# VoiceRecognitionGroup3.net
KiCad netlist of a schematic drawn in EAGLE
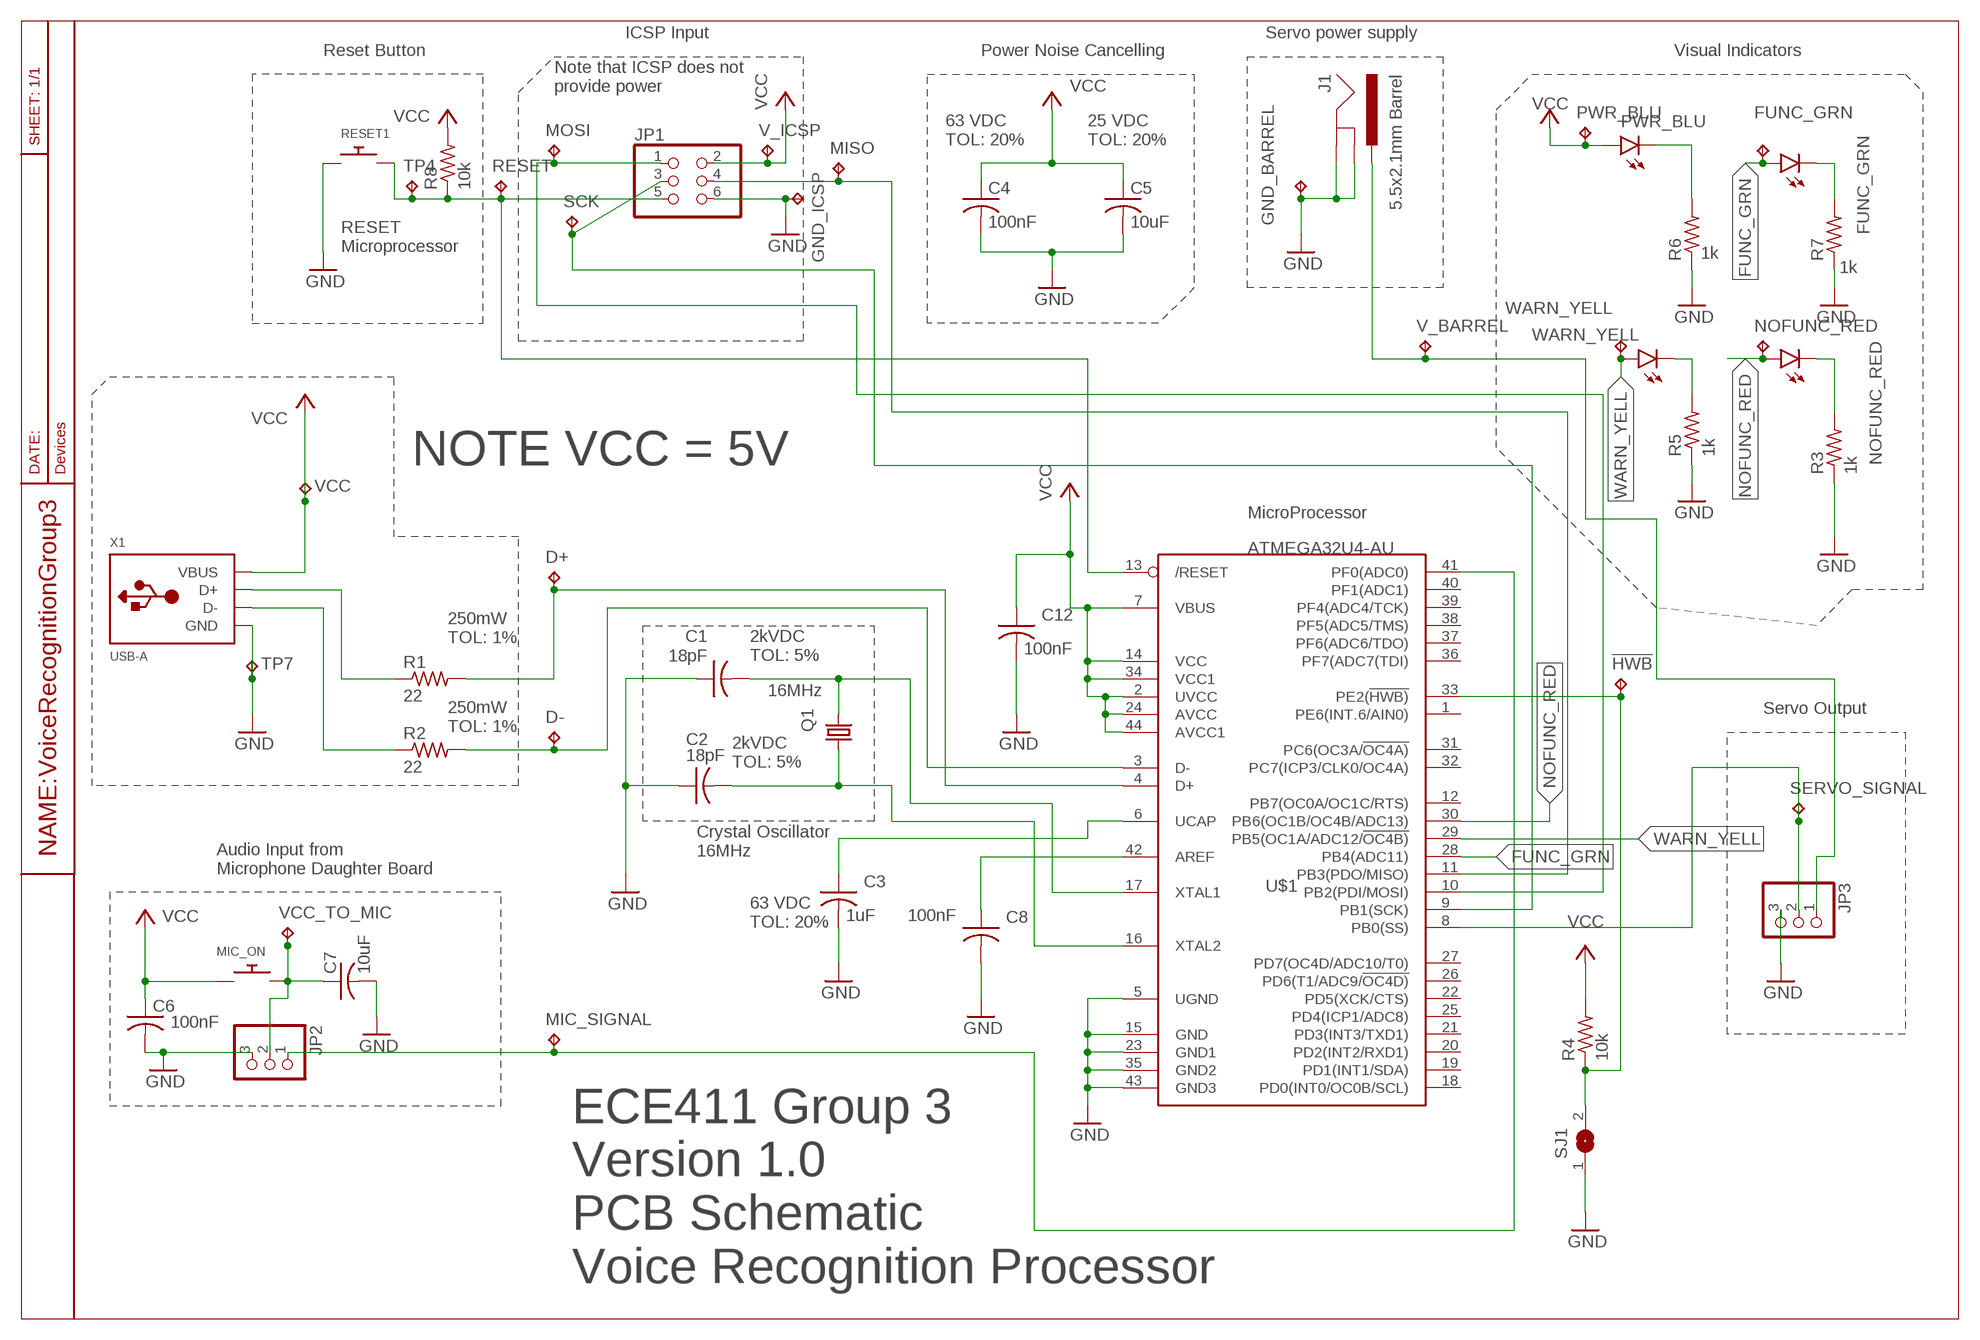
[diagram p0: schematic, sheet 1]

(export (version "E")
  (design (tool "Eeschema 10.0.6"))
  (components
    (comp (ref "!HWB")
      (value "TPTP15SQ")
      (footprint "eagle-import:TP15SQ")
      (libsource (lib "eagle-import") (part "TPTP15SQ"))
    )
    (comp (ref "C1")
      (value "18pF")
      (footprint "eagle-import:C1206")
      (libsource (lib "eagle-import") (part "C-USC1206"))
    )
    (comp (ref "C2")
      (value "18pF")
      (footprint "eagle-import:C1206")
      (libsource (lib "eagle-import") (part "C-USC1206"))
    )
    (comp (ref "C3")
      (value "1uF")
      (footprint "eagle-import:C1206")
      (libsource (lib "eagle-import") (part "C-USC1206"))
    )
    (comp (ref "C4")
      (value "100nF")
      (footprint "eagle-import:C1206")
      (libsource (lib "eagle-import") (part "C-USC1206"))
    )
    (comp (ref "C5")
      (value "10uF")
      (footprint "eagle-import:C1206")
      (libsource (lib "eagle-import") (part "C-USC1206"))
    )
    (comp (ref "C6")
      (value "100nF")
      (footprint "eagle-import:C1206")
      (libsource (lib "eagle-import") (part "C-USC1206"))
    )
    (comp (ref "C7")
      (value "10uF")
      (footprint "eagle-import:C1206")
      (libsource (lib "eagle-import") (part "C-USC1206"))
    )
    (comp (ref "C8")
      (value "100nF")
      (footprint "eagle-import:C1206")
      (libsource (lib "eagle-import") (part "C-USC1206"))
    )
    (comp (ref "C12")
      (value "100nF")
      (footprint "eagle-import:C1206")
      (libsource (lib "eagle-import") (part "C-USC1206"))
    )
    (comp (ref "D+")
      (value "TPTP15SQ")
      (footprint "eagle-import:TP15SQ")
      (libsource (lib "eagle-import") (part "TPTP15SQ"))
    )
    (comp (ref "D-")
      (value "TPTP15SQ")
      (footprint "eagle-import:TP15SQ")
      (libsource (lib "eagle-import") (part "TPTP15SQ"))
    )
    (comp (ref "FUNC_GRN")
      (value "TPTP15SQ")
      (footprint "eagle-import:TP15SQ")
      (libsource (lib "eagle-import") (part "TPTP15SQ"))
    )
    (comp (ref "GND_BARREL")
      (value "TPTP15SQ")
      (footprint "eagle-import:TP15SQ")
      (libsource (lib "eagle-import") (part "TPTP15SQ"))
    )
    (comp (ref "GND_ICSP")
      (value "TPTP15SQ")
      (footprint "eagle-import:TP15SQ")
      (libsource (lib "eagle-import") (part "TPTP15SQ"))
    )
    (comp (ref "J1")
      (value "5.5x2.1mm Barrel")
      (footprint "eagle-import:POWER_JACK_SMD")
      (libsource (lib "eagle-import") (part "POWER_JACKSMD"))
    )
    (comp (ref "JP1")
      (value "PINHD-2X3")
      (footprint "eagle-import:2X03")
      (libsource (lib "eagle-import") (part "PINHD-2X3"))
    )
    (comp (ref "JP2")
      (value "PINHD-1X3")
      (footprint "eagle-import:1X03")
      (libsource (lib "eagle-import") (part "PINHD-1X3"))
    )
    (comp (ref "JP3")
      (value "PINHD-1X3")
      (footprint "eagle-import:1X03")
      (libsource (lib "eagle-import") (part "PINHD-1X3"))
    )
    (comp (ref "LED2")
      (value "LEDSMT1206")
      (footprint "eagle-import:1206")
      (libsource (lib "eagle-import") (part "LEDSMT1206"))
    )
    (comp (ref "LED3")
      (value "LEDSMT1206")
      (footprint "eagle-import:1206")
      (libsource (lib "eagle-import") (part "LEDSMT1206"))
    )
    (comp (ref "LED4")
      (value "LEDSMT1206")
      (footprint "eagle-import:1206")
      (libsource (lib "eagle-import") (part "LEDSMT1206"))
    )
    (comp (ref "MIC_ON")
      (value "SWITCH_PUSHBUTTONC&K_KSS")
      (footprint "eagle-import:BTN_CK_KSS")
      (libsource (lib "eagle-import") (part "SWITCH_PUSHBUTTONC&K_KSS"))
    )
    (comp (ref "MIC_SIGNAL")
      (value "TPTP15SQ")
      (footprint "eagle-import:TP15SQ")
      (libsource (lib "eagle-import") (part "TPTP15SQ"))
    )
    (comp (ref "MISO")
      (value "TPTP15SQ")
      (footprint "eagle-import:TP15SQ")
      (libsource (lib "eagle-import") (part "TPTP15SQ"))
    )
    (comp (ref "MOSI")
      (value "TPTP15SQ")
      (footprint "eagle-import:TP15SQ")
      (libsource (lib "eagle-import") (part "TPTP15SQ"))
    )
    (comp (ref "NOFUNC_RED")
      (value "TPTP15SQ")
      (footprint "eagle-import:TP15SQ")
      (libsource (lib "eagle-import") (part "TPTP15SQ"))
    )
    (comp (ref "PWR-BLU")
      (value "LEDSMT1206")
      (footprint "eagle-import:1206")
      (libsource (lib "eagle-import") (part "LEDSMT1206"))
    )
    (comp (ref "PWR_BLU")
      (value "TPTP15SQ")
      (footprint "eagle-import:TP15SQ")
      (libsource (lib "eagle-import") (part "TPTP15SQ"))
    )
    (comp (ref "Q1")
      (value "16MHz")
      (footprint "eagle-import:CTS406")
      (libsource (lib "eagle-import") (part "CRYSTALCTS406"))
    )
    (comp (ref "R1")
      (value "22")
      (footprint "eagle-import:M1206")
      (libsource (lib "eagle-import") (part "R-US_M1206"))
    )
    (comp (ref "R2")
      (value "22")
      (footprint "eagle-import:M1206")
      (libsource (lib "eagle-import") (part "R-US_M1206"))
    )
    (comp (ref "R3")
      (value "1k")
      (footprint "eagle-import:M1206")
      (libsource (lib "eagle-import") (part "R-US_M1206"))
    )
    (comp (ref "R4")
      (value "10k")
      (footprint "eagle-import:M1206")
      (libsource (lib "eagle-import") (part "R-US_M1206"))
    )
    (comp (ref "R5")
      (value "1k")
      (footprint "eagle-import:M1206")
      (libsource (lib "eagle-import") (part "R-US_M1206"))
    )
    (comp (ref "R6")
      (value "1k")
      (footprint "eagle-import:M1206")
      (libsource (lib "eagle-import") (part "R-US_M1206"))
    )
    (comp (ref "R7")
      (value "1k")
      (footprint "eagle-import:M1206")
      (libsource (lib "eagle-import") (part "R-US_M1206"))
    )
    (comp (ref "R8")
      (value "10k")
      (footprint "eagle-import:M1206")
      (libsource (lib "eagle-import") (part "R-US_M1206"))
    )
    (comp (ref "RESET")
      (value "TPTP15SQ")
      (footprint "eagle-import:TP15SQ")
      (libsource (lib "eagle-import") (part "TPTP15SQ"))
    )
    (comp (ref "RESET1")
      (value "SWITCH_PUSHBUTTONC&K_KSS")
      (footprint "eagle-import:BTN_CK_KSS")
      (libsource (lib "eagle-import") (part "SWITCH_PUSHBUTTONC&K_KSS"))
    )
    (comp (ref "SCK")
      (value "TPTP15SQ")
      (footprint "eagle-import:TP15SQ")
      (libsource (lib "eagle-import") (part "TPTP15SQ"))
    )
    (comp (ref "SERVO_SIGNAL")
      (value "TPTP15SQ")
      (footprint "eagle-import:TP15SQ")
      (libsource (lib "eagle-import") (part "TPTP15SQ"))
    )
    (comp (ref "SJ1")
      (value "SJW")
      (footprint "eagle-import:SJW")
      (libsource (lib "eagle-import") (part "SJW"))
    )
    (comp (ref "TP4")
      (value "TPTP15SQ")
      (footprint "eagle-import:TP15SQ")
      (libsource (lib "eagle-import") (part "TPTP15SQ"))
    )
    (comp (ref "TP7")
      (value "TPTP15SQ")
      (footprint "eagle-import:TP15SQ")
      (libsource (lib "eagle-import") (part "TPTP15SQ"))
    )
    (comp (ref "U$1")
      (value "ATMEGA32U4-AU")
      (footprint "eagle-import:TQFP44")
      (libsource (lib "eagle-import") (part "ATMEGA32U4-AU"))
    )
    (comp (ref "VCC")
      (value "TPTP15SQ")
      (footprint "eagle-import:TP15SQ")
      (libsource (lib "eagle-import") (part "TPTP15SQ"))
    )
    (comp (ref "VCC_TO_MIC")
      (value "TPTP15SQ")
      (footprint "eagle-import:TP15SQ")
      (libsource (lib "eagle-import") (part "TPTP15SQ"))
    )
    (comp (ref "V_BARREL")
      (value "TPTP15SQ")
      (footprint "eagle-import:TP15SQ")
      (libsource (lib "eagle-import") (part "TPTP15SQ"))
    )
    (comp (ref "V_ICSP")
      (value "TPTP15SQ")
      (footprint "eagle-import:TP15SQ")
      (libsource (lib "eagle-import") (part "TPTP15SQ"))
    )
    (comp (ref "WARN_YELL")
      (value "TPTP15SQ")
      (footprint "eagle-import:TP15SQ")
      (libsource (lib "eagle-import") (part "TPTP15SQ"))
    )
    (comp (ref "X1")
      (value "USB-A")
      (footprint "eagle-import:MOLEX_480371000")
      (libsource (lib "eagle-import") (part "USB-A"))
    )
  )
  (nets
    (net (code "1") (name "FUNC_GRN") (class "Default")
      (node (ref "FUNC_GRN") (pin "TP") (pinfunction "TP_TP") (pintype "input"))
      (node (ref "LED2") (pin "A") (pinfunction "A_A") (pintype "passive"))
      (node (ref "U$1") (pin "28") (pinfunction "PB4(ADC11)_28") (pintype "bidirectional"))
    )
    (net (code "2") (name "GND") (class "Default")
      (node (ref "C1") (pin "1") (pinfunction "1_1") (pintype "passive"))
      (node (ref "C12") (pin "2") (pinfunction "2_2") (pintype "passive"))
      (node (ref "C2") (pin "1") (pinfunction "1_1") (pintype "passive"))
      (node (ref "C3") (pin "2") (pinfunction "2_2") (pintype "passive"))
      (node (ref "C4") (pin "2") (pinfunction "2_2") (pintype "passive"))
      (node (ref "C5") (pin "2") (pinfunction "2_2") (pintype "passive"))
      (node (ref "C6") (pin "2") (pinfunction "2_2") (pintype "passive"))
      (node (ref "C7") (pin "2") (pinfunction "2_2") (pintype "passive"))
      (node (ref "C8") (pin "2") (pinfunction "2_2") (pintype "passive"))
      (node (ref "GND_BARREL") (pin "TP") (pinfunction "TP_TP") (pintype "input"))
      (node (ref "GND_ICSP") (pin "TP") (pinfunction "TP_TP") (pintype "input"))
      (node (ref "J1") (pin "GND") (pinfunction "GNDBREAK_GND") (pintype "bidirectional"))
      (node (ref "J1") (pin "P$4") (pinfunction "GND_P$4") (pintype "bidirectional"))
      (node (ref "JP1") (pin "6") (pinfunction "6_6") (pintype "passive"))
      (node (ref "JP2") (pin "3") (pinfunction "3_3") (pintype "passive"))
      (node (ref "JP3") (pin "3") (pinfunction "3_3") (pintype "passive"))
      (node (ref "R3") (pin "1") (pinfunction "1_1") (pintype "passive"))
      (node (ref "R5") (pin "1") (pinfunction "1_1") (pintype "passive"))
      (node (ref "R6") (pin "1") (pinfunction "1_1") (pintype "passive"))
      (node (ref "R7") (pin "1") (pinfunction "1_1") (pintype "passive"))
      (node (ref "RESET1") (pin "P$1") (pinfunction "P$1_P$1") (pintype "passive"))
      (node (ref "SJ1") (pin "1") (pinfunction "1_1") (pintype "passive"))
      (node (ref "TP7") (pin "TP") (pinfunction "TP_TP") (pintype "input"))
      (node (ref "U$1") (pin "15") (pinfunction "GND_15") (pintype "bidirectional"))
      (node (ref "U$1") (pin "23") (pinfunction "GND1_23") (pintype "bidirectional"))
      (node (ref "U$1") (pin "35") (pinfunction "GND2_35") (pintype "bidirectional"))
      (node (ref "U$1") (pin "43") (pinfunction "GND3_43") (pintype "bidirectional"))
      (node (ref "U$1") (pin "5") (pinfunction "UGND_5") (pintype "bidirectional"))
      (node (ref "X1") (pin "4") (pinfunction "GND_4") (pintype "power_in"))
    )
    (net (code "3") (name "NOFUNC_RED") (class "Default")
      (node (ref "LED3") (pin "A") (pinfunction "A_A") (pintype "passive"))
      (node (ref "NOFUNC_RED") (pin "TP") (pinfunction "TP_TP") (pintype "input"))
      (node (ref "U$1") (pin "30") (pinfunction "PB6(OC1B/OC4B/ADC13)_30") (pintype "bidirectional"))
    )
    (net (code "4") (name "Net-(C7-Pad1)") (class "Default")
      (node (ref "C7") (pin "1") (pinfunction "1_1") (pintype "passive"))
      (node (ref "JP2") (pin "2") (pinfunction "2_2") (pintype "passive"))
      (node (ref "MIC_ON") (pin "P$2") (pinfunction "P$2_P$2") (pintype "passive"))
      (node (ref "VCC_TO_MIC") (pin "TP") (pinfunction "TP_TP") (pintype "input"))
    )
    (net (code "5") (name "Net-(J1-PWR)") (class "Default")
      (node (ref "J1") (pin "VIN0") (pinfunction "PWR_VIN0") (pintype "bidirectional"))
      (node (ref "JP3") (pin "1") (pinfunction "1_1") (pintype "passive"))
      (node (ref "V_BARREL") (pin "TP") (pinfunction "TP_TP") (pintype "input"))
    )
    (net (code "6") (name "Net-(LED2-PadC)") (class "Default")
      (node (ref "LED2") (pin "C") (pinfunction "C_C") (pintype "passive"))
      (node (ref "R7") (pin "2") (pinfunction "2_2") (pintype "passive"))
    )
    (net (code "7") (name "Net-(LED3-PadC)") (class "Default")
      (node (ref "LED3") (pin "C") (pinfunction "C_C") (pintype "passive"))
      (node (ref "R3") (pin "2") (pinfunction "2_2") (pintype "passive"))
    )
    (net (code "8") (name "Net-(LED4-PadC)") (class "Default")
      (node (ref "LED4") (pin "C") (pinfunction "C_C") (pintype "passive"))
      (node (ref "R5") (pin "2") (pinfunction "2_2") (pintype "passive"))
    )
    (net (code "9") (name "Net-(PWR-BLU-PadC)") (class "Default")
      (node (ref "PWR-BLU") (pin "C") (pinfunction "C_C") (pintype "passive"))
      (node (ref "R6") (pin "2") (pinfunction "2_2") (pintype "passive"))
    )
    (net (code "10") (name "Net-(Q1-2)") (class "Default")
      (node (ref "C1") (pin "2") (pinfunction "2_2") (pintype "passive"))
      (node (ref "Q1") (pin "3") (pinfunction "2_3") (pintype "passive"))
      (node (ref "U$1") (pin "17") (pinfunction "XTAL1_17") (pintype "bidirectional"))
    )
    (net (code "11") (name "Net-(U$1-AREF)") (class "Default")
      (node (ref "C8") (pin "1") (pinfunction "1_1") (pintype "passive"))
      (node (ref "U$1") (pin "42") (pinfunction "AREF_42") (pintype "bidirectional"))
    )
    (net (code "12") (name "Net-(U$1-D+)") (class "Default")
      (node (ref "D+") (pin "TP") (pinfunction "TP_TP") (pintype "input"))
      (node (ref "R1") (pin "2") (pinfunction "2_2") (pintype "passive"))
      (node (ref "U$1") (pin "4") (pinfunction "D+_4") (pintype "bidirectional"))
    )
    (net (code "13") (name "Net-(U$1-D-)") (class "Default")
      (node (ref "D-") (pin "TP") (pinfunction "TP_TP") (pintype "input"))
      (node (ref "R2") (pin "2") (pinfunction "2_2") (pintype "passive"))
      (node (ref "U$1") (pin "3") (pinfunction "D-_3") (pintype "bidirectional"))
    )
    (net (code "14") (name "Net-(U$1-PB0(SS))") (class "Default")
      (node (ref "JP3") (pin "2") (pinfunction "2_2") (pintype "passive"))
      (node (ref "SERVO_SIGNAL") (pin "TP") (pinfunction "TP_TP") (pintype "input"))
      (node (ref "U$1") (pin "8") (pinfunction "PB0(SS)_8") (pintype "bidirectional"))
    )
    (net (code "15") (name "Net-(U$1-PB1(SCK))") (class "Default")
      (node (ref "JP1") (pin "3") (pinfunction "3_3") (pintype "passive"))
      (node (ref "SCK") (pin "TP") (pinfunction "TP_TP") (pintype "input"))
      (node (ref "U$1") (pin "9") (pinfunction "PB1(SCK)_9") (pintype "bidirectional"))
    )
    (net (code "16") (name "Net-(U$1-PB2(PDI{slash}MOSI))") (class "Default")
      (node (ref "JP1") (pin "1") (pinfunction "1_1") (pintype "passive"))
      (node (ref "MOSI") (pin "TP") (pinfunction "TP_TP") (pintype "input"))
      (node (ref "U$1") (pin "10") (pinfunction "PB2(PDI/MOSI)_10") (pintype "bidirectional"))
    )
    (net (code "17") (name "Net-(U$1-PB3(PDO{slash}MISO))") (class "Default")
      (node (ref "JP1") (pin "4") (pinfunction "4_4") (pintype "passive"))
      (node (ref "MISO") (pin "TP") (pinfunction "TP_TP") (pintype "input"))
      (node (ref "U$1") (pin "11") (pinfunction "PB3(PDO/MISO)_11") (pintype "bidirectional"))
    )
    (net (code "18") (name "Net-(U$1-PE2(~{HWB}))") (class "Default")
      (node (ref "!HWB") (pin "TP") (pinfunction "TP_TP") (pintype "input"))
      (node (ref "R4") (pin "1") (pinfunction "1_1") (pintype "passive"))
      (node (ref "SJ1") (pin "2") (pinfunction "2_2") (pintype "passive"))
      (node (ref "U$1") (pin "33") (pinfunction "PE2(~{HWB})_33") (pintype "bidirectional"))
    )
    (net (code "19") (name "Net-(U$1-PF0(ADC0))") (class "Default")
      (node (ref "JP2") (pin "1") (pinfunction "1_1") (pintype "passive"))
      (node (ref "MIC_SIGNAL") (pin "TP") (pinfunction "TP_TP") (pintype "input"))
      (node (ref "U$1") (pin "41") (pinfunction "PF0(ADC0)_41") (pintype "bidirectional"))
    )
    (net (code "20") (name "Net-(U$1-UCAP)") (class "Default")
      (node (ref "C3") (pin "1") (pinfunction "1_1") (pintype "passive"))
      (node (ref "U$1") (pin "6") (pinfunction "UCAP_6") (pintype "bidirectional"))
    )
    (net (code "21") (name "Net-(U$1-XTAL2)") (class "Default")
      (node (ref "C2") (pin "2") (pinfunction "2_2") (pintype "passive"))
      (node (ref "Q1") (pin "1") (pinfunction "1_1") (pintype "passive"))
      (node (ref "U$1") (pin "16") (pinfunction "XTAL2_16") (pintype "bidirectional"))
    )
    (net (code "22") (name "Net-(U$1-{slash}RESET)") (class "Default")
      (node (ref "JP1") (pin "5") (pinfunction "5_5") (pintype "passive"))
      (node (ref "R8") (pin "1") (pinfunction "1_1") (pintype "passive"))
      (node (ref "RESET") (pin "TP") (pinfunction "TP_TP") (pintype "input"))
      (node (ref "RESET1") (pin "P$2") (pinfunction "P$2_P$2") (pintype "passive"))
      (node (ref "TP4") (pin "TP") (pinfunction "TP_TP") (pintype "input"))
      (node (ref "U$1") (pin "13") (pinfunction "/RESET_13") (pintype "bidirectional"))
    )
    (net (code "23") (name "Net-(X1-D+)") (class "Default")
      (node (ref "R1") (pin "1") (pinfunction "1_1") (pintype "passive"))
      (node (ref "X1") (pin "3") (pinfunction "D+_3") (pintype "bidirectional"))
    )
    (net (code "24") (name "Net-(X1-D-)") (class "Default")
      (node (ref "R2") (pin "1") (pinfunction "1_1") (pintype "passive"))
      (node (ref "X1") (pin "2") (pinfunction "D-_2") (pintype "bidirectional"))
    )
    (net (code "25") (name "VCC") (class "Default")
      (node (ref "C12") (pin "1") (pinfunction "1_1") (pintype "passive"))
      (node (ref "C4") (pin "1") (pinfunction "1_1") (pintype "passive"))
      (node (ref "C5") (pin "1") (pinfunction "1_1") (pintype "passive"))
      (node (ref "C6") (pin "1") (pinfunction "1_1") (pintype "passive"))
      (node (ref "JP1") (pin "2") (pinfunction "2_2") (pintype "passive"))
      (node (ref "MIC_ON") (pin "P$1") (pinfunction "P$1_P$1") (pintype "passive"))
      (node (ref "PWR-BLU") (pin "A") (pinfunction "A_A") (pintype "passive"))
      (node (ref "PWR_BLU") (pin "TP") (pinfunction "TP_TP") (pintype "input"))
      (node (ref "R4") (pin "2") (pinfunction "2_2") (pintype "passive"))
      (node (ref "R8") (pin "2") (pinfunction "2_2") (pintype "passive"))
      (node (ref "U$1") (pin "14") (pinfunction "VCC_14") (pintype "bidirectional"))
      (node (ref "U$1") (pin "2") (pinfunction "UVCC_2") (pintype "bidirectional"))
      (node (ref "U$1") (pin "24") (pinfunction "AVCC_24") (pintype "bidirectional"))
      (node (ref "U$1") (pin "34") (pinfunction "VCC1_34") (pintype "bidirectional"))
      (node (ref "U$1") (pin "44") (pinfunction "AVCC1_44") (pintype "bidirectional"))
      (node (ref "U$1") (pin "7") (pinfunction "VBUS_7") (pintype "bidirectional"))
      (node (ref "VCC") (pin "TP") (pinfunction "TP_TP") (pintype "input"))
      (node (ref "V_ICSP") (pin "TP") (pinfunction "TP_TP") (pintype "input"))
      (node (ref "X1") (pin "1") (pinfunction "VBUS_1") (pintype "power_in"))
    )
    (net (code "26") (name "WARN_YELL") (class "Default")
      (node (ref "LED4") (pin "A") (pinfunction "A_A") (pintype "passive"))
      (node (ref "U$1") (pin "29") (pinfunction "PB5(OC1A/ADC12/~{OC4B})_29") (pintype "bidirectional"))
      (node (ref "WARN_YELL") (pin "TP") (pinfunction "TP_TP") (pintype "input"))
    )
    (net (code "27") (name "unconnected-(U$1-PB7(OC0A{slash}OC1C{slash}RTS)-Pad12)") (class "Default")
      (node (ref "U$1") (pin "12") (pinfunction "PB7(OC0A/OC1C/RTS)_12") (pintype "bidirectional"))
    )
    (net (code "28") (name "unconnected-(U$1-PC6(OC3A{slash}~{OC4A})-Pad31)") (class "Default")
      (node (ref "U$1") (pin "31") (pinfunction "PC6(OC3A/~{OC4A})_31") (pintype "bidirectional"))
    )
    (net (code "29") (name "unconnected-(U$1-PC7(ICP3{slash}CLK0{slash}OC4A)-Pad32)") (class "Default")
      (node (ref "U$1") (pin "32") (pinfunction "PC7(ICP3/CLK0/OC4A)_32") (pintype "bidirectional"))
    )
    (net (code "30") (name "unconnected-(U$1-PD0(INT0{slash}OC0B{slash}SCL)-Pad18)") (class "Default")
      (node (ref "U$1") (pin "18") (pinfunction "PD0(INT0/OC0B/SCL)_18") (pintype "bidirectional"))
    )
    (net (code "31") (name "unconnected-(U$1-PD1(INT1{slash}SDA)-Pad19)") (class "Default")
      (node (ref "U$1") (pin "19") (pinfunction "PD1(INT1/SDA)_19") (pintype "bidirectional"))
    )
    (net (code "32") (name "unconnected-(U$1-PD2(INT2{slash}RXD1)-Pad20)") (class "Default")
      (node (ref "U$1") (pin "20") (pinfunction "PD2(INT2/RXD1)_20") (pintype "bidirectional"))
    )
    (net (code "33") (name "unconnected-(U$1-PD3(INT3{slash}TXD1)-Pad21)") (class "Default")
      (node (ref "U$1") (pin "21") (pinfunction "PD3(INT3/TXD1)_21") (pintype "bidirectional"))
    )
    (net (code "34") (name "unconnected-(U$1-PD4(ICP1{slash}ADC8)-Pad25)") (class "Default")
      (node (ref "U$1") (pin "25") (pinfunction "PD4(ICP1/ADC8)_25") (pintype "bidirectional"))
    )
    (net (code "35") (name "unconnected-(U$1-PD5(XCK{slash}CTS)-Pad22)") (class "Default")
      (node (ref "U$1") (pin "22") (pinfunction "PD5(XCK/CTS)_22") (pintype "bidirectional"))
    )
    (net (code "36") (name "unconnected-(U$1-PD6(T1{slash}ADC9{slash}~{OC4D})-Pad26)") (class "Default")
      (node (ref "U$1") (pin "26") (pinfunction "PD6(T1/ADC9/~{OC4D})_26") (pintype "bidirectional"))
    )
    (net (code "37") (name "unconnected-(U$1-PD7(OC4D{slash}ADC10{slash}T0)-Pad27)") (class "Default")
      (node (ref "U$1") (pin "27") (pinfunction "PD7(OC4D/ADC10/T0)_27") (pintype "bidirectional"))
    )
    (net (code "38") (name "unconnected-(U$1-PE6(INT.6{slash}AIN0)-Pad1)") (class "Default")
      (node (ref "U$1") (pin "1") (pinfunction "PE6(INT.6/AIN0)_1") (pintype "bidirectional"))
    )
    (net (code "39") (name "unconnected-(U$1-PF1(ADC1)-Pad40)") (class "Default")
      (node (ref "U$1") (pin "40") (pinfunction "PF1(ADC1)_40") (pintype "bidirectional"))
    )
    (net (code "40") (name "unconnected-(U$1-PF4(ADC4{slash}TCK)-Pad39)") (class "Default")
      (node (ref "U$1") (pin "39") (pinfunction "PF4(ADC4/TCK)_39") (pintype "bidirectional"))
    )
    (net (code "41") (name "unconnected-(U$1-PF5(ADC5{slash}TMS)-Pad38)") (class "Default")
      (node (ref "U$1") (pin "38") (pinfunction "PF5(ADC5/TMS)_38") (pintype "bidirectional"))
    )
    (net (code "42") (name "unconnected-(U$1-PF6(ADC6{slash}TDO)-Pad37)") (class "Default")
      (node (ref "U$1") (pin "37") (pinfunction "PF6(ADC6/TDO)_37") (pintype "bidirectional"))
    )
    (net (code "43") (name "unconnected-(U$1-PF7(ADC7(TDI)-Pad36)") (class "Default")
      (node (ref "U$1") (pin "36") (pinfunction "PF7(ADC7(TDI)_36") (pintype "bidirectional"))
    )
  )
)
